# Battery_Charging.net
KiCad netlist of a schematic drawn in Altium Designer
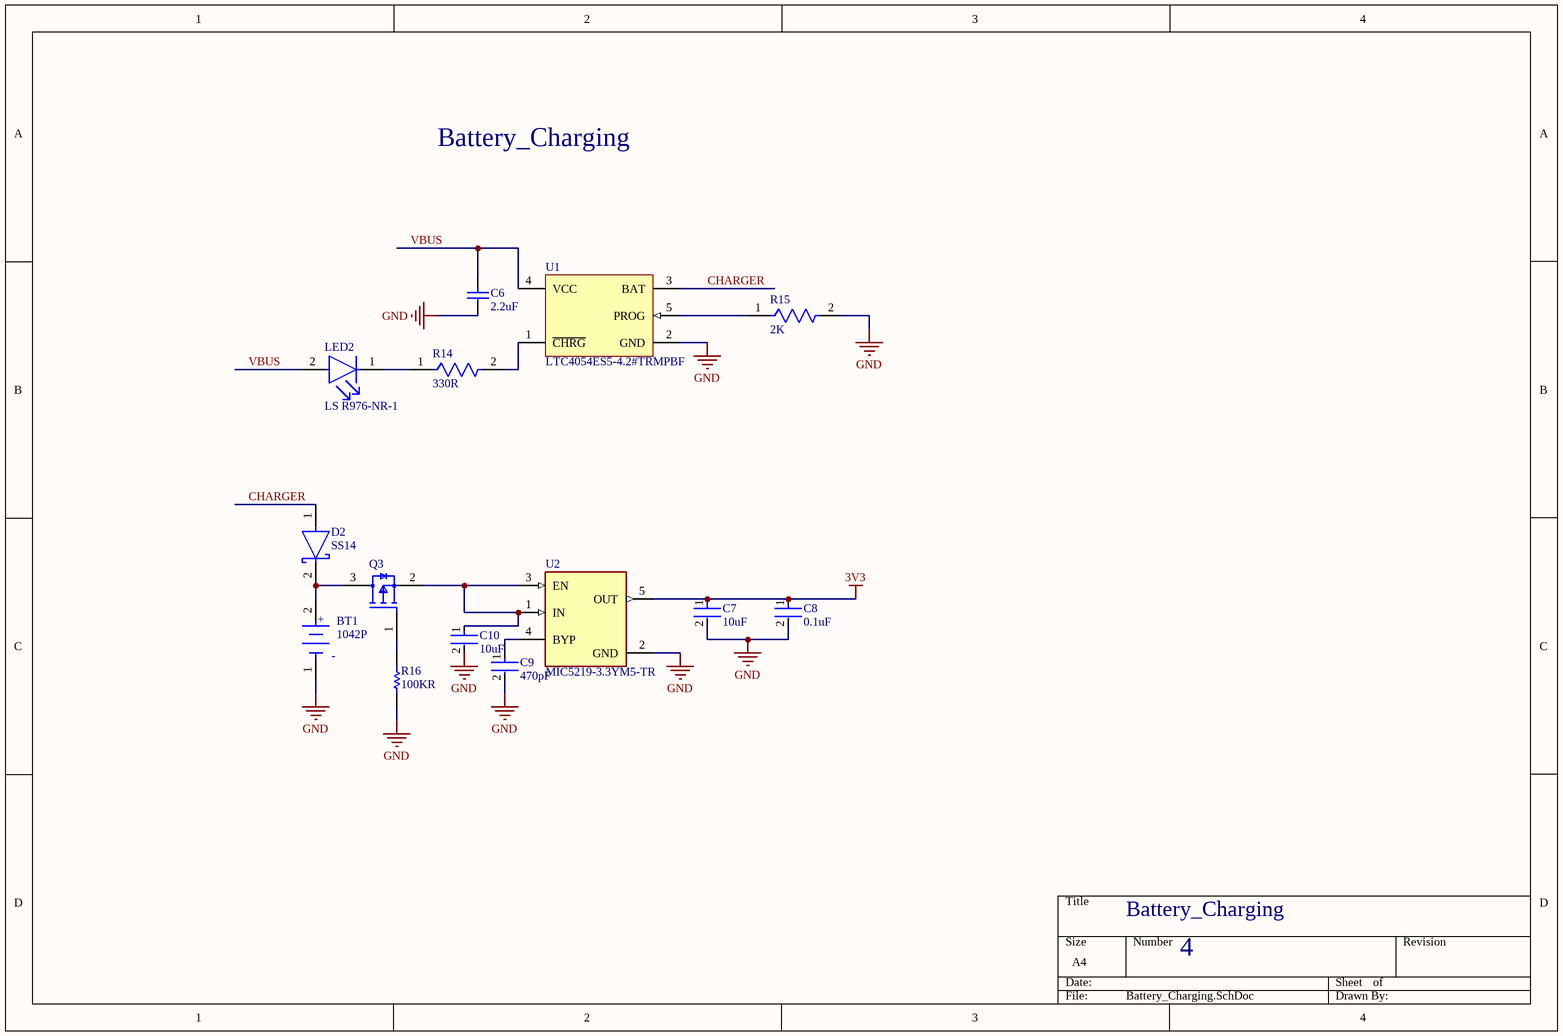
[diagram p0: Battery_Charging.SchDoc]

(export (version "E")
  (design (tool "Eeschema 10.0.6"))
  (components
    (comp (ref "BT1")
      (value "1042P")
      (footprint "FP-1042P-MFG")
      (description "BATTERY HOLDER 18650 SMD TAB")
      (libsource (lib "Altium Content Vault") (part "60d3b5b901a8747834971d0eb8cf3fd"))
    )
    (comp (ref "C6")
      (value "2.2uF")
      (footprint "CAPC2013X145X50ML20T25")
      (fields (field (name "PART NUMBER") "C0805C225K9PACTU") (field (name "MANUFACTURER") "Kemet"))
      (libsource (lib "Altium Content Vault") (part "CAP"))
    )
    (comp (ref "C7")
      (value "10uF")
      (footprint "FP-CL21-IPC_C")
      (description "CL21 Series 0805 10uF 6.3V ±10% Tolerance X6S Multilayer Ceramic Chip Capacitor")
      (fields (field (name "TOLERANCE") "10%"))
      (libsource (lib "Altium Content Vault") (part "b4654b650e69147ec39a6b967a45e02"))
    )
    (comp (ref "C8")
      (value "0.1uF")
      (footprint "FP-CC0805-EA-MFG")
      (description "CAP CER X7R 0805")
      (libsource (lib "Altium Content Vault") (part "b4654b650e69147ec39a6b967a45e02"))
    )
    (comp (ref "C9")
      (value "470pF")
      (footprint "FP-C0603C-CF-MFG")
      (description "CAP CER 470PF 10V X7R 0603")
      (fields
        (field (name "OCTOPART") "https://octopart.com/c0603c471k8ractu-kemet-9138956")
        (field (name "MANUFACTURER") "KEMET")
      )
      (libsource (lib "Altium Content Vault") (part "b4654b650e69147ec39a6b967a45e02"))
    )
    (comp (ref "C10")
      (value "10uF")
      (footprint "FP-CL21-IPC_A")
      (description "CL21 Series 0805 10uF 6.3V ±10% Tolerance X5R Multilayer Ceramic Chip Capacitor")
      (fields (field (name "TOLERANCE") "10%"))
      (libsource (lib "Altium Content Vault") (part "b4654b650e69147ec39a6b967a45e02"))
    )
    (comp (ref "D2")
      (value "SS14")
      (footprint "FP-403AE-MFG")
      (description "DIODE SCHOTTKY 40V 1A SMA")
      (fields
        (field (name "MANUFACTURER") "ON Semiconductor")
        (field (name "OCTOPART") "https://octopart.com/ss14-on+semiconductor-29205033")
      )
      (libsource (lib "Altium Content Vault") (part "360ad2f4ac25a952324d13796385471"))
    )
    (comp (ref "LED2")
      (value "LS R976-NR-1")
      (footprint "FP-LS_R976-MFG")
      (description "LED RED DIFFUSED 0805 SMD")
      (libsource (lib "Altium Content Vault") (part "8706943c75ba83719d021d2fdc84c58"))
    )
    (comp (ref "Q3")
      (value "SI2301BDS-T1-GE3")
      (footprint "FP-S-03946-MFG")
      (description "SI2301BDS-T1-GE3 Trans Mosfet P-ch Si 20V 2.2A 3-PIN SOT-23 T/r / Mosfet P-ch 20V 2.2A SOT23-3")
      (libsource (lib "Altium Content Vault") (part "274ba75a4227b453460520a6808ef61"))
    )
    (comp (ref "R14")
      (value "330R")
      (footprint "FP-CPF0603-MFG")
      (description "RES SMD 330Ω 0.1% 1/16W 0603")
      (fields
        (field (name "MANUFACTURER") "TE Connectivity")
        (field (name "OCTOPART") "https://octopart.com/cpf0603b330re1-te+connectivity-9539413")
      )
      (libsource (lib "Altium Content Vault") (part "1029c3af85768c4190bb7ad29bc67b5"))
    )
    (comp (ref "R15")
      (value "2K")
      (footprint "FP-RMCF0603-IPC_A")
      (description "2kΩ ±1% 0.1W 0603 Thick Film Chip Resistor AEC-Q200 compliant")
      (fields (field (name "TOLERANCE") "1%"))
      (libsource (lib "Altium Content Vault") (part "1029c3af85768c4190bb7ad29bc67b5"))
    )
    (comp (ref "R16")
      (value "100KR")
      (footprint "RESC2013X70X40ML20T20")
      (fields (field (name "PART NUMBER") "ERJ-6ENF1003V") (field (name "MANUFACTURER") "Panasonic"))
      (libsource (lib "Altium Content Vault") (part "RES"))
    )
    (comp (ref "U1")
      (value "LTC4054ES5-4.2#TRMPBF")
      (footprint "LT-S5-5-TSOT-23_M")
      (fields (field (name "MANUFACTURER") "Linear Technology"))
      (libsource (lib "Altium Content Vault") (part "LT-LTC4054-S5-5"))
    )
    (comp (ref "U2")
      (value "MIC5219-3.3YM5-TR")
      (footprint "FP-SOT23-5LD-PL-1-IPC_C")
      (description "IC REG LINEAR 3.3V 500MA SOT23-5")
      (libsource (lib "Altium Content Vault") (part "16b36b16d6b7b40c29ab14718bc3058"))
    )
  )
  (nets
    (net (code "1") (name "/CHARGER") (class "Default")
      (node (ref "D2") (pin "1") (pinfunction "A_1") (pintype "passive"))
      (node (ref "U1") (pin "3") (pinfunction "BAT_3") (pintype "power_in"))
    )
    (net (code "2") (name "/VBUS") (class "Default")
      (node (ref "C6") (pin "2") (pinfunction "2_2") (pintype "passive"))
      (node (ref "LED2") (pin "2") (pinfunction "A_2") (pintype "passive"))
      (node (ref "U1") (pin "4") (pinfunction "VCC_4") (pintype "power_in"))
    )
    (net (code "3") (name "3V3") (class "Default")
      (node (ref "C7") (pin "1") (pinfunction "1_1") (pintype "passive"))
      (node (ref "C8") (pin "1") (pinfunction "1_1") (pintype "passive"))
      (node (ref "U2") (pin "5") (pinfunction "OUT_5") (pintype "output"))
    )
    (net (code "4") (name "GND") (class "Default")
      (node (ref "BT1") (pin "1") (pinfunction "C_1") (pintype "passive"))
      (node (ref "C10") (pin "2") (pinfunction "2_2") (pintype "passive"))
      (node (ref "C6") (pin "1") (pinfunction "1_1") (pintype "passive"))
      (node (ref "C7") (pin "2") (pinfunction "2_2") (pintype "passive"))
      (node (ref "C8") (pin "2") (pinfunction "2_2") (pintype "passive"))
      (node (ref "C9") (pin "2") (pinfunction "2_2") (pintype "passive"))
      (node (ref "R15") (pin "2") (pinfunction "2_2") (pintype "passive"))
      (node (ref "R16") (pin "2") (pinfunction "2_2") (pintype "passive"))
      (node (ref "U1") (pin "2") (pinfunction "GND_2") (pintype "power_in"))
      (node (ref "U2") (pin "2") (pinfunction "GND_2") (pintype "power_in"))
    )
    (net (code "5") (name "Net-(BT1-A)") (class "Default")
      (node (ref "BT1") (pin "2") (pinfunction "A_2") (pintype "passive"))
      (node (ref "D2") (pin "2") (pinfunction "C_2") (pintype "passive"))
      (node (ref "Q3") (pin "3") (pinfunction "D_3") (pintype "passive"))
    )
    (net (code "6") (name "Net-(LED2-C)") (class "Default")
      (node (ref "LED2") (pin "1") (pinfunction "C_1") (pintype "passive"))
      (node (ref "R14") (pin "1") (pinfunction "1_1") (pintype "passive"))
    )
    (net (code "7") (name "Net-(Q3-G)") (class "Default")
      (node (ref "Q3") (pin "1") (pinfunction "G_1") (pintype "passive"))
      (node (ref "R16") (pin "1") (pinfunction "1_1") (pintype "passive"))
    )
    (net (code "8") (name "Net-(Q3-S)") (class "Default")
      (node (ref "C10") (pin "1") (pinfunction "1_1") (pintype "passive"))
      (node (ref "Q3") (pin "2") (pinfunction "S_2") (pintype "passive"))
      (node (ref "U2") (pin "1") (pinfunction "IN_1") (pintype "input"))
      (node (ref "U2") (pin "3") (pinfunction "EN_3") (pintype "input"))
    )
    (net (code "9") (name "Net-(U1-PROG)") (class "Default")
      (node (ref "R15") (pin "1") (pinfunction "1_1") (pintype "passive"))
      (node (ref "U1") (pin "5") (pinfunction "PROG_5") (pintype "input"))
    )
    (net (code "10") (name "Net-(U1-~{CHRG})") (class "Default")
      (node (ref "R14") (pin "2") (pinfunction "2_2") (pintype "passive"))
      (node (ref "U1") (pin "1") (pinfunction "~{CHRG}_1") (pintype "tri_state"))
    )
    (net (code "11") (name "Net-(U2-BYP)") (class "Default")
      (node (ref "C9") (pin "1") (pinfunction "1_1") (pintype "passive"))
      (node (ref "U2") (pin "4") (pinfunction "BYP_4") (pintype "passive"))
    )
  )
)
